# EAGLE_FILE.net
KiCad netlist of a schematic drawn in EAGLE
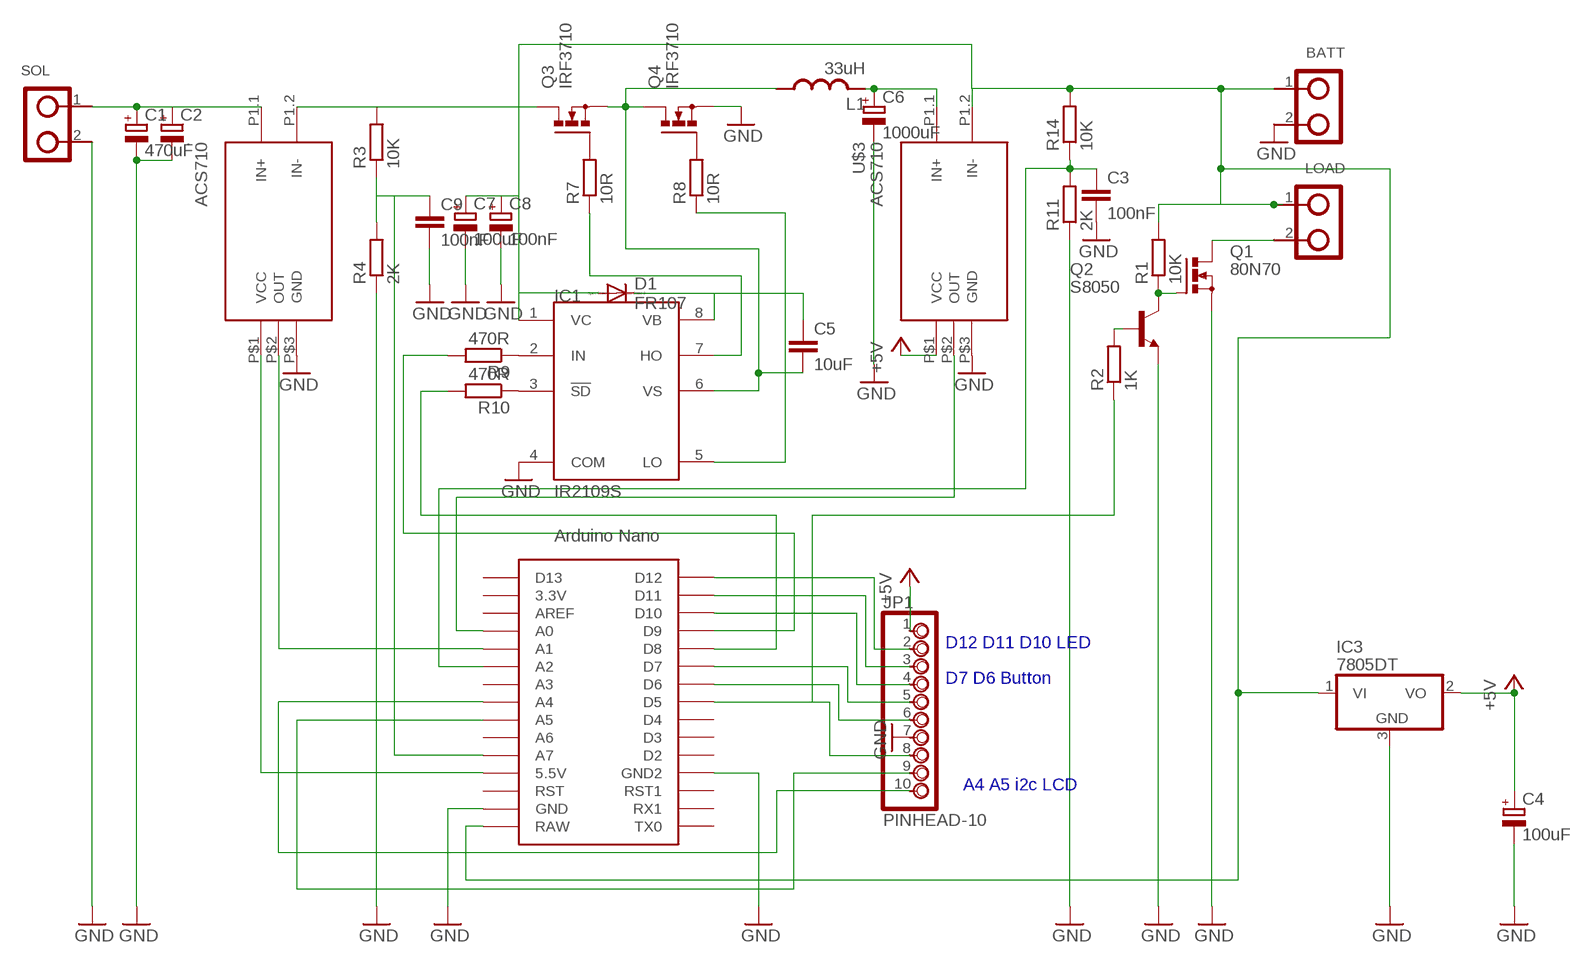
[diagram p0: schematic, sheet 1]

(export (version "E")
  (design (tool "Eeschema 10.0.6"))
  (components
    (comp (ref ".")
      (value "ACS710")
      (footprint "eagle-import:CURRENT-SENSOR-ACS712#IC")
      (libsource (lib "eagle-import") (part "CURRENT-SENSOR-ACS712#IC"))
    )
    (comp (ref "BATT")
      (value "DOMINO-2")
      (footprint "eagle-import:DOMI-2")
      (libsource (lib "eagle-import") (part "DOMINO-2"))
    )
    (comp (ref "C1")
      (value "470uF")
      (footprint "eagle-import:E5-13")
      (libsource (lib "eagle-import") (part "CPOL-EUE5-13"))
    )
    (comp (ref "C2")
      (value "CPOL-EUE5-13")
      (footprint "eagle-import:E5-13")
      (libsource (lib "eagle-import") (part "CPOL-EUE5-13"))
    )
    (comp (ref "C3")
      (value "100nF")
      (footprint "eagle-import:C1206")
      (libsource (lib "eagle-import") (part "C-EUC1206"))
    )
    (comp (ref "C4")
      (value "100uF")
      (footprint "eagle-import:SMC_D")
      (libsource (lib "eagle-import") (part "rcl_CPOL-EUSMCD"))
    )
    (comp (ref "C5")
      (value "10uF")
      (footprint "eagle-import:C1812")
      (libsource (lib "eagle-import") (part "C-EUC1812"))
    )
    (comp (ref "C6")
      (value "1000uF")
      (footprint "eagle-import:E5-13")
      (libsource (lib "eagle-import") (part "CPOL-EUE5-13"))
    )
    (comp (ref "C7")
      (value "100uF")
      (footprint "eagle-import:SMC_D")
      (libsource (lib "eagle-import") (part "rcl_CPOL-EUSMCD"))
    )
    (comp (ref "C8")
      (value "100nF")
      (footprint "eagle-import:SMC_D")
      (libsource (lib "eagle-import") (part "rcl_CPOL-EUSMCD"))
    )
    (comp (ref "C9")
      (value "100nF")
      (footprint "eagle-import:C1206")
      (libsource (lib "eagle-import") (part "C-EUC1206"))
    )
    (comp (ref "D1")
      (value "FR107")
      (footprint "eagle-import:SMB")
      (libsource (lib "eagle-import") (part "DIODE-SMB"))
    )
    (comp (ref "IC1")
      (value "IR2109S")
      (footprint "eagle-import:SO08")
      (libsource (lib "eagle-import") (part "IR2109S"))
    )
    (comp (ref "IC3")
      (value "7805DT")
      (footprint "eagle-import:TO252")
      (libsource (lib "eagle-import") (part "78DT05"))
    )
    (comp (ref "JP1")
      (value "PINHEAD-10")
      (footprint "eagle-import:PINHEAD-10")
      (libsource (lib "eagle-import") (part "PINHEAD-10"))
    )
    (comp (ref "L1")
      (value "33uH")
      (footprint "eagle-import:L-10")
      (libsource (lib "eagle-import") (part "L-10"))
    )
    (comp (ref "LOAD")
      (value "DOMINO-2")
      (footprint "eagle-import:DOMI-2")
      (libsource (lib "eagle-import") (part "DOMINO-2"))
    )
    (comp (ref "Q1")
      (value "80N70")
      (footprint "eagle-import:TO220BV")
      (libsource (lib "eagle-import") (part "IRF512"))
    )
    (comp (ref "Q2")
      (value "S8050")
      (footprint "eagle-import:TO92")
      (libsource (lib "eagle-import") (part "2N4416"))
    )
    (comp (ref "Q3")
      (value "IRF3710")
      (footprint "eagle-import:TO220BV")
      (libsource (lib "eagle-import") (part "IRF512"))
    )
    (comp (ref "Q4")
      (value "IRF3710")
      (footprint "eagle-import:TO220BV")
      (libsource (lib "eagle-import") (part "lbr_IRF512"))
    )
    (comp (ref "R1")
      (value "10K")
      (footprint "eagle-import:R1206")
      (libsource (lib "eagle-import") (part "R-EU_R1206"))
    )
    (comp (ref "R2")
      (value "1K")
      (footprint "eagle-import:R1206")
      (libsource (lib "eagle-import") (part "R-EU_R1206"))
    )
    (comp (ref "R3")
      (value "10K")
      (footprint "eagle-import:R1206")
      (libsource (lib "eagle-import") (part "R-EU_R1206"))
    )
    (comp (ref "R4")
      (value "2K")
      (footprint "eagle-import:R1206")
      (libsource (lib "eagle-import") (part "R-EU_R1206"))
    )
    (comp (ref "R7")
      (value "10R")
      (footprint "eagle-import:R1206")
      (libsource (lib "eagle-import") (part "R-EU_R1206"))
    )
    (comp (ref "R8")
      (value "10R")
      (footprint "eagle-import:R1206")
      (libsource (lib "eagle-import") (part "R-EU_R1206"))
    )
    (comp (ref "R9")
      (value "470R")
      (footprint "eagle-import:R1206")
      (libsource (lib "eagle-import") (part "R-EU_R1206"))
    )
    (comp (ref "R10")
      (value "470R")
      (footprint "eagle-import:R1206")
      (libsource (lib "eagle-import") (part "R-EU_R1206"))
    )
    (comp (ref "R11")
      (value "2K")
      (footprint "eagle-import:R1206")
      (libsource (lib "eagle-import") (part "R-EU_R1206"))
    )
    (comp (ref "R14")
      (value "10K")
      (footprint "eagle-import:R1206")
      (libsource (lib "eagle-import") (part "R-EU_R1206"))
    )
    (comp (ref "SOL")
      (value "DOMINO-2")
      (footprint "eagle-import:DOMI-2")
      (libsource (lib "eagle-import") (part "DOMINO-2"))
    )
    (comp (ref "U$1")
      (value "NANO")
      (footprint "eagle-import:NANO")
      (libsource (lib "eagle-import") (part "NANO"))
    )
    (comp (ref "U$3")
      (value "ACS710")
      (footprint "eagle-import:CURRENT-SENSOR-ACS712#IC")
      (libsource (lib "eagle-import") (part "CURRENT-SENSOR-ACS712#IC"))
    )
  )
  (nets
    (net (code "1") (name "+5V") (class "Default")
      (node (ref "C4") (pin "+") (pinfunction "+_+") (pintype "passive"))
      (node (ref "IC3") (pin "2") (pinfunction "VO_2") (pintype "passive"))
      (node (ref "JP1") (pin "1") (pinfunction "1_1") (pintype "passive"))
      (node (ref "U$3") (pin "P$1") (pinfunction "VCC_P$1") (pintype "power_in"))
    )
    (net (code "2") (name "GND") (class "Default")
      (node (ref ".") (pin "P$3") (pinfunction "GND_P$3") (pintype "power_in"))
      (node (ref "BATT") (pin "2") (pinfunction "2_2") (pintype "bidirectional"))
      (node (ref "C1") (pin "-") (pinfunction "-_-") (pintype "passive"))
      (node (ref "C2") (pin "-") (pinfunction "-_-") (pintype "passive"))
      (node (ref "C3") (pin "2") (pinfunction "2_2") (pintype "passive"))
      (node (ref "C4") (pin "-") (pinfunction "-_-") (pintype "passive"))
      (node (ref "C6") (pin "-") (pinfunction "-_-") (pintype "passive"))
      (node (ref "C7") (pin "-") (pinfunction "-_-") (pintype "passive"))
      (node (ref "C8") (pin "-") (pinfunction "-_-") (pintype "passive"))
      (node (ref "C9") (pin "2") (pinfunction "2_2") (pintype "passive"))
      (node (ref "IC1") (pin "4") (pinfunction "COM_4") (pintype "power_in"))
      (node (ref "IC3") (pin "3") (pinfunction "GND_3") (pintype "passive"))
      (node (ref "JP1") (pin "7") (pinfunction "7_7") (pintype "passive"))
      (node (ref "Q1") (pin "S") (pinfunction "S_S") (pintype "passive"))
      (node (ref "Q2") (pin "3") (pinfunction "E_3") (pintype "passive"))
      (node (ref "Q4") (pin "S") (pinfunction "S_S") (pintype "passive"))
      (node (ref "R11") (pin "1") (pinfunction "1_1") (pintype "passive"))
      (node (ref "R4") (pin "1") (pinfunction "1_1") (pintype "passive"))
      (node (ref "SOL") (pin "2") (pinfunction "2_2") (pintype "bidirectional"))
      (node (ref "U$1") (pin "GND") (pinfunction "GND_GND") (pintype "bidirectional"))
      (node (ref "U$1") (pin "GND1") (pinfunction "GND2_GND1") (pintype "bidirectional"))
      (node (ref "U$3") (pin "P$3") (pinfunction "GND_P$3") (pintype "power_in"))
    )
    (net (code "3") (name "Net-(.-IN+)") (class "Default")
      (node (ref ".") (pin "P1.1") (pinfunction "IN+_P1.1") (pintype "bidirectional"))
      (node (ref "C1") (pin "+") (pinfunction "+_+") (pintype "passive"))
      (node (ref "C2") (pin "+") (pinfunction "+_+") (pintype "passive"))
      (node (ref "SOL") (pin "1") (pinfunction "1_1") (pintype "bidirectional"))
    )
    (net (code "4") (name "Net-(.-IN-)") (class "Default")
      (node (ref ".") (pin "P1.2") (pinfunction "IN-_P1.2") (pintype "bidirectional"))
      (node (ref "Q3") (pin "D") (pinfunction "D_D") (pintype "passive"))
      (node (ref "R3") (pin "2") (pinfunction "2_2") (pintype "passive"))
    )
    (net (code "5") (name "Net-(.-OUT)") (class "Default")
      (node (ref ".") (pin "P$2") (pinfunction "OUT_P$2") (pintype "output"))
      (node (ref "U$1") (pin "A1") (pinfunction "A1_A1") (pintype "bidirectional"))
    )
    (net (code "6") (name "Net-(.-VCC)") (class "Default")
      (node (ref ".") (pin "P$1") (pinfunction "VCC_P$1") (pintype "power_in"))
      (node (ref "U$1") (pin "5V") (pinfunction "5.5V_5V") (pintype "bidirectional"))
    )
    (net (code "7") (name "Net-(C3-Pad1)") (class "Default")
      (node (ref "C3") (pin "1") (pinfunction "1_1") (pintype "passive"))
      (node (ref "R11") (pin "2") (pinfunction "2_2") (pintype "passive"))
      (node (ref "R14") (pin "1") (pinfunction "1_1") (pintype "passive"))
      (node (ref "U$1") (pin "A2") (pinfunction "A2_A2") (pintype "bidirectional"))
    )
    (net (code "8") (name "Net-(C9-Pad1)") (class "Default")
      (node (ref "C9") (pin "1") (pinfunction "1_1") (pintype "passive"))
      (node (ref "R3") (pin "1") (pinfunction "1_1") (pintype "passive"))
      (node (ref "R4") (pin "2") (pinfunction "2_2") (pintype "passive"))
      (node (ref "U$1") (pin "A7") (pinfunction "A7_A7") (pintype "bidirectional"))
    )
    (net (code "9") (name "Net-(IC1-HO)") (class "Default")
      (node (ref "IC1") (pin "7") (pinfunction "HO_7") (pintype "output"))
      (node (ref "R7") (pin "1") (pinfunction "1_1") (pintype "passive"))
    )
    (net (code "10") (name "Net-(IC1-IN)") (class "Default")
      (node (ref "IC1") (pin "2") (pinfunction "IN_2") (pintype "input"))
      (node (ref "R9") (pin "1") (pinfunction "1_1") (pintype "passive"))
    )
    (net (code "11") (name "Net-(IC1-LO)") (class "Default")
      (node (ref "IC1") (pin "5") (pinfunction "LO_5") (pintype "output"))
      (node (ref "R8") (pin "1") (pinfunction "1_1") (pintype "passive"))
    )
    (net (code "12") (name "Net-(IC1-VB)") (class "Default")
      (node (ref "C5") (pin "1") (pinfunction "1_1") (pintype "passive"))
      (node (ref "D1") (pin "C") (pinfunction "C_C") (pintype "passive"))
      (node (ref "IC1") (pin "8") (pinfunction "VB_8") (pintype "power_in"))
    )
    (net (code "13") (name "Net-(IC1-VC)") (class "Default")
      (node (ref "BATT") (pin "1") (pinfunction "1_1") (pintype "bidirectional"))
      (node (ref "C7") (pin "+") (pinfunction "+_+") (pintype "passive"))
      (node (ref "C8") (pin "+") (pinfunction "+_+") (pintype "passive"))
      (node (ref "D1") (pin "A") (pinfunction "A_A") (pintype "passive"))
      (node (ref "IC1") (pin "1") (pinfunction "VC_1") (pintype "power_in"))
      (node (ref "IC3") (pin "1") (pinfunction "VI_1") (pintype "input"))
      (node (ref "LOAD") (pin "1") (pinfunction "1_1") (pintype "bidirectional"))
      (node (ref "R1") (pin "2") (pinfunction "2_2") (pintype "passive"))
      (node (ref "R14") (pin "2") (pinfunction "2_2") (pintype "passive"))
      (node (ref "U$1") (pin "RAW") (pinfunction "RAW_RAW") (pintype "bidirectional"))
      (node (ref "U$3") (pin "P1.2") (pinfunction "IN-_P1.2") (pintype "bidirectional"))
    )
    (net (code "14") (name "Net-(IC1-VS)") (class "Default")
      (node (ref "C5") (pin "2") (pinfunction "2_2") (pintype "passive"))
      (node (ref "IC1") (pin "6") (pinfunction "VS_6") (pintype "power_in"))
      (node (ref "L1") (pin "1") (pinfunction "1_1") (pintype "passive"))
      (node (ref "Q3") (pin "S") (pinfunction "S_S") (pintype "passive"))
      (node (ref "Q4") (pin "D") (pinfunction "D_D") (pintype "passive"))
    )
    (net (code "15") (name "Net-(IC1-~{SD})") (class "Default")
      (node (ref "IC1") (pin "3") (pinfunction "~{SD}_3") (pintype "input"))
      (node (ref "R10") (pin "1") (pinfunction "1_1") (pintype "passive"))
    )
    (net (code "16") (name "Net-(JP1-Pad2)") (class "Default")
      (node (ref "JP1") (pin "2") (pinfunction "2_2") (pintype "passive"))
      (node (ref "U$1") (pin "D12") (pinfunction "D12_D12") (pintype "bidirectional"))
    )
    (net (code "17") (name "Net-(JP1-Pad3)") (class "Default")
      (node (ref "JP1") (pin "3") (pinfunction "3_3") (pintype "passive"))
      (node (ref "U$1") (pin "D11") (pinfunction "D11_D11") (pintype "bidirectional"))
    )
    (net (code "18") (name "Net-(JP1-Pad4)") (class "Default")
      (node (ref "JP1") (pin "4") (pinfunction "4_4") (pintype "passive"))
      (node (ref "U$1") (pin "D10") (pinfunction "D10_D10") (pintype "bidirectional"))
    )
    (net (code "19") (name "Net-(JP1-Pad5)") (class "Default")
      (node (ref "JP1") (pin "5") (pinfunction "5_5") (pintype "passive"))
      (node (ref "U$1") (pin "D7") (pinfunction "D7_D7") (pintype "bidirectional"))
    )
    (net (code "20") (name "Net-(JP1-Pad6)") (class "Default")
      (node (ref "JP1") (pin "6") (pinfunction "6_6") (pintype "passive"))
      (node (ref "U$1") (pin "D6") (pinfunction "D6_D6") (pintype "bidirectional"))
    )
    (net (code "21") (name "Net-(JP1-Pad8)") (class "Default")
      (node (ref "JP1") (pin "8") (pinfunction "8_8") (pintype "passive"))
      (node (ref "R2") (pin "1") (pinfunction "1_1") (pintype "passive"))
      (node (ref "U$1") (pin "D5") (pinfunction "D5_D5") (pintype "bidirectional"))
    )
    (net (code "22") (name "Net-(JP1-Pad9)") (class "Default")
      (node (ref "JP1") (pin "9") (pinfunction "9_9") (pintype "passive"))
      (node (ref "U$1") (pin "A5") (pinfunction "A5_A5") (pintype "bidirectional"))
    )
    (net (code "23") (name "Net-(JP1-Pad10)") (class "Default")
      (node (ref "JP1") (pin "10") (pinfunction "10_10") (pintype "passive"))
      (node (ref "U$1") (pin "A4") (pinfunction "A4_A4") (pintype "bidirectional"))
    )
    (net (code "24") (name "Net-(LOAD-Pad2)") (class "Default")
      (node (ref "LOAD") (pin "2") (pinfunction "2_2") (pintype "bidirectional"))
      (node (ref "Q1") (pin "D") (pinfunction "D_D") (pintype "passive"))
    )
    (net (code "25") (name "Net-(Q2-B)") (class "Default")
      (node (ref "Q2") (pin "2") (pinfunction "B_2") (pintype "passive"))
      (node (ref "R2") (pin "2") (pinfunction "2_2") (pintype "passive"))
    )
    (net (code "26") (name "Net-(Q2-C)") (class "Default")
      (node (ref "Q1") (pin "G") (pinfunction "G_G") (pintype "passive"))
      (node (ref "Q2") (pin "1") (pinfunction "C_1") (pintype "passive"))
      (node (ref "R1") (pin "1") (pinfunction "1_1") (pintype "passive"))
    )
    (net (code "27") (name "Net-(Q3-PadG)") (class "Default")
      (node (ref "Q3") (pin "G") (pinfunction "G_G") (pintype "passive"))
      (node (ref "R7") (pin "2") (pinfunction "2_2") (pintype "passive"))
    )
    (net (code "28") (name "Net-(Q4-PadG)") (class "Default")
      (node (ref "Q4") (pin "G") (pinfunction "G_G") (pintype "passive"))
      (node (ref "R8") (pin "2") (pinfunction "2_2") (pintype "passive"))
    )
    (net (code "29") (name "Net-(R9-Pad2)") (class "Default")
      (node (ref "R9") (pin "2") (pinfunction "2_2") (pintype "passive"))
      (node (ref "U$1") (pin "D9") (pinfunction "D9_D9") (pintype "bidirectional"))
    )
    (net (code "30") (name "Net-(R10-Pad2)") (class "Default")
      (node (ref "R10") (pin "2") (pinfunction "2_2") (pintype "passive"))
      (node (ref "U$1") (pin "D8") (pinfunction "D8_D8") (pintype "bidirectional"))
    )
    (net (code "31") (name "Net-(U$3-IN+)") (class "Default")
      (node (ref "C6") (pin "+") (pinfunction "+_+") (pintype "passive"))
      (node (ref "L1") (pin "2") (pinfunction "2_2") (pintype "passive"))
      (node (ref "U$3") (pin "P1.1") (pinfunction "IN+_P1.1") (pintype "bidirectional"))
    )
    (net (code "32") (name "Net-(U$3-OUT)") (class "Default")
      (node (ref "U$1") (pin "A0") (pinfunction "A0_A0") (pintype "bidirectional"))
      (node (ref "U$3") (pin "P$2") (pinfunction "OUT_P$2") (pintype "output"))
    )
    (net (code "33") (name "unconnected-(U$1-Pad3.3V)") (class "Default")
      (node (ref "U$1") (pin "3.3V") (pinfunction "3.3V_3.3V") (pintype "bidirectional"))
    )
    (net (code "34") (name "unconnected-(U$1-PadA3)") (class "Default")
      (node (ref "U$1") (pin "A3") (pinfunction "A3_A3") (pintype "bidirectional"))
    )
    (net (code "35") (name "unconnected-(U$1-PadA6)") (class "Default")
      (node (ref "U$1") (pin "A6") (pinfunction "A6_A6") (pintype "bidirectional"))
    )
    (net (code "36") (name "unconnected-(U$1-PadAREF)") (class "Default")
      (node (ref "U$1") (pin "AREF") (pinfunction "AREF_AREF") (pintype "bidirectional"))
    )
    (net (code "37") (name "unconnected-(U$1-PadD2)") (class "Default")
      (node (ref "U$1") (pin "D2") (pinfunction "D2_D2") (pintype "bidirectional"))
    )
    (net (code "38") (name "unconnected-(U$1-PadD3)") (class "Default")
      (node (ref "U$1") (pin "D3") (pinfunction "D3_D3") (pintype "bidirectional"))
    )
    (net (code "39") (name "unconnected-(U$1-PadD4)") (class "Default")
      (node (ref "U$1") (pin "D4") (pinfunction "D4_D4") (pintype "bidirectional"))
    )
    (net (code "40") (name "unconnected-(U$1-PadD13)") (class "Default")
      (node (ref "U$1") (pin "D13") (pinfunction "D13_D13") (pintype "bidirectional"))
    )
    (net (code "41") (name "unconnected-(U$1-PadRST)") (class "Default")
      (node (ref "U$1") (pin "RST") (pinfunction "RST_RST") (pintype "bidirectional"))
    )
    (net (code "42") (name "unconnected-(U$1-PadRST1)") (class "Default")
      (node (ref "U$1") (pin "RST1") (pinfunction "RST1_RST1") (pintype "bidirectional"))
    )
    (net (code "43") (name "unconnected-(U$1-PadRX1)") (class "Default")
      (node (ref "U$1") (pin "RX1") (pinfunction "RX1_RX1") (pintype "bidirectional"))
    )
    (net (code "44") (name "unconnected-(U$1-PadTX0)") (class "Default")
      (node (ref "U$1") (pin "TX0") (pinfunction "TX0_TX0") (pintype "bidirectional"))
    )
  )
)
